# Turnstile_route1.net
KiCad netlist of a schematic drawn in EAGLE
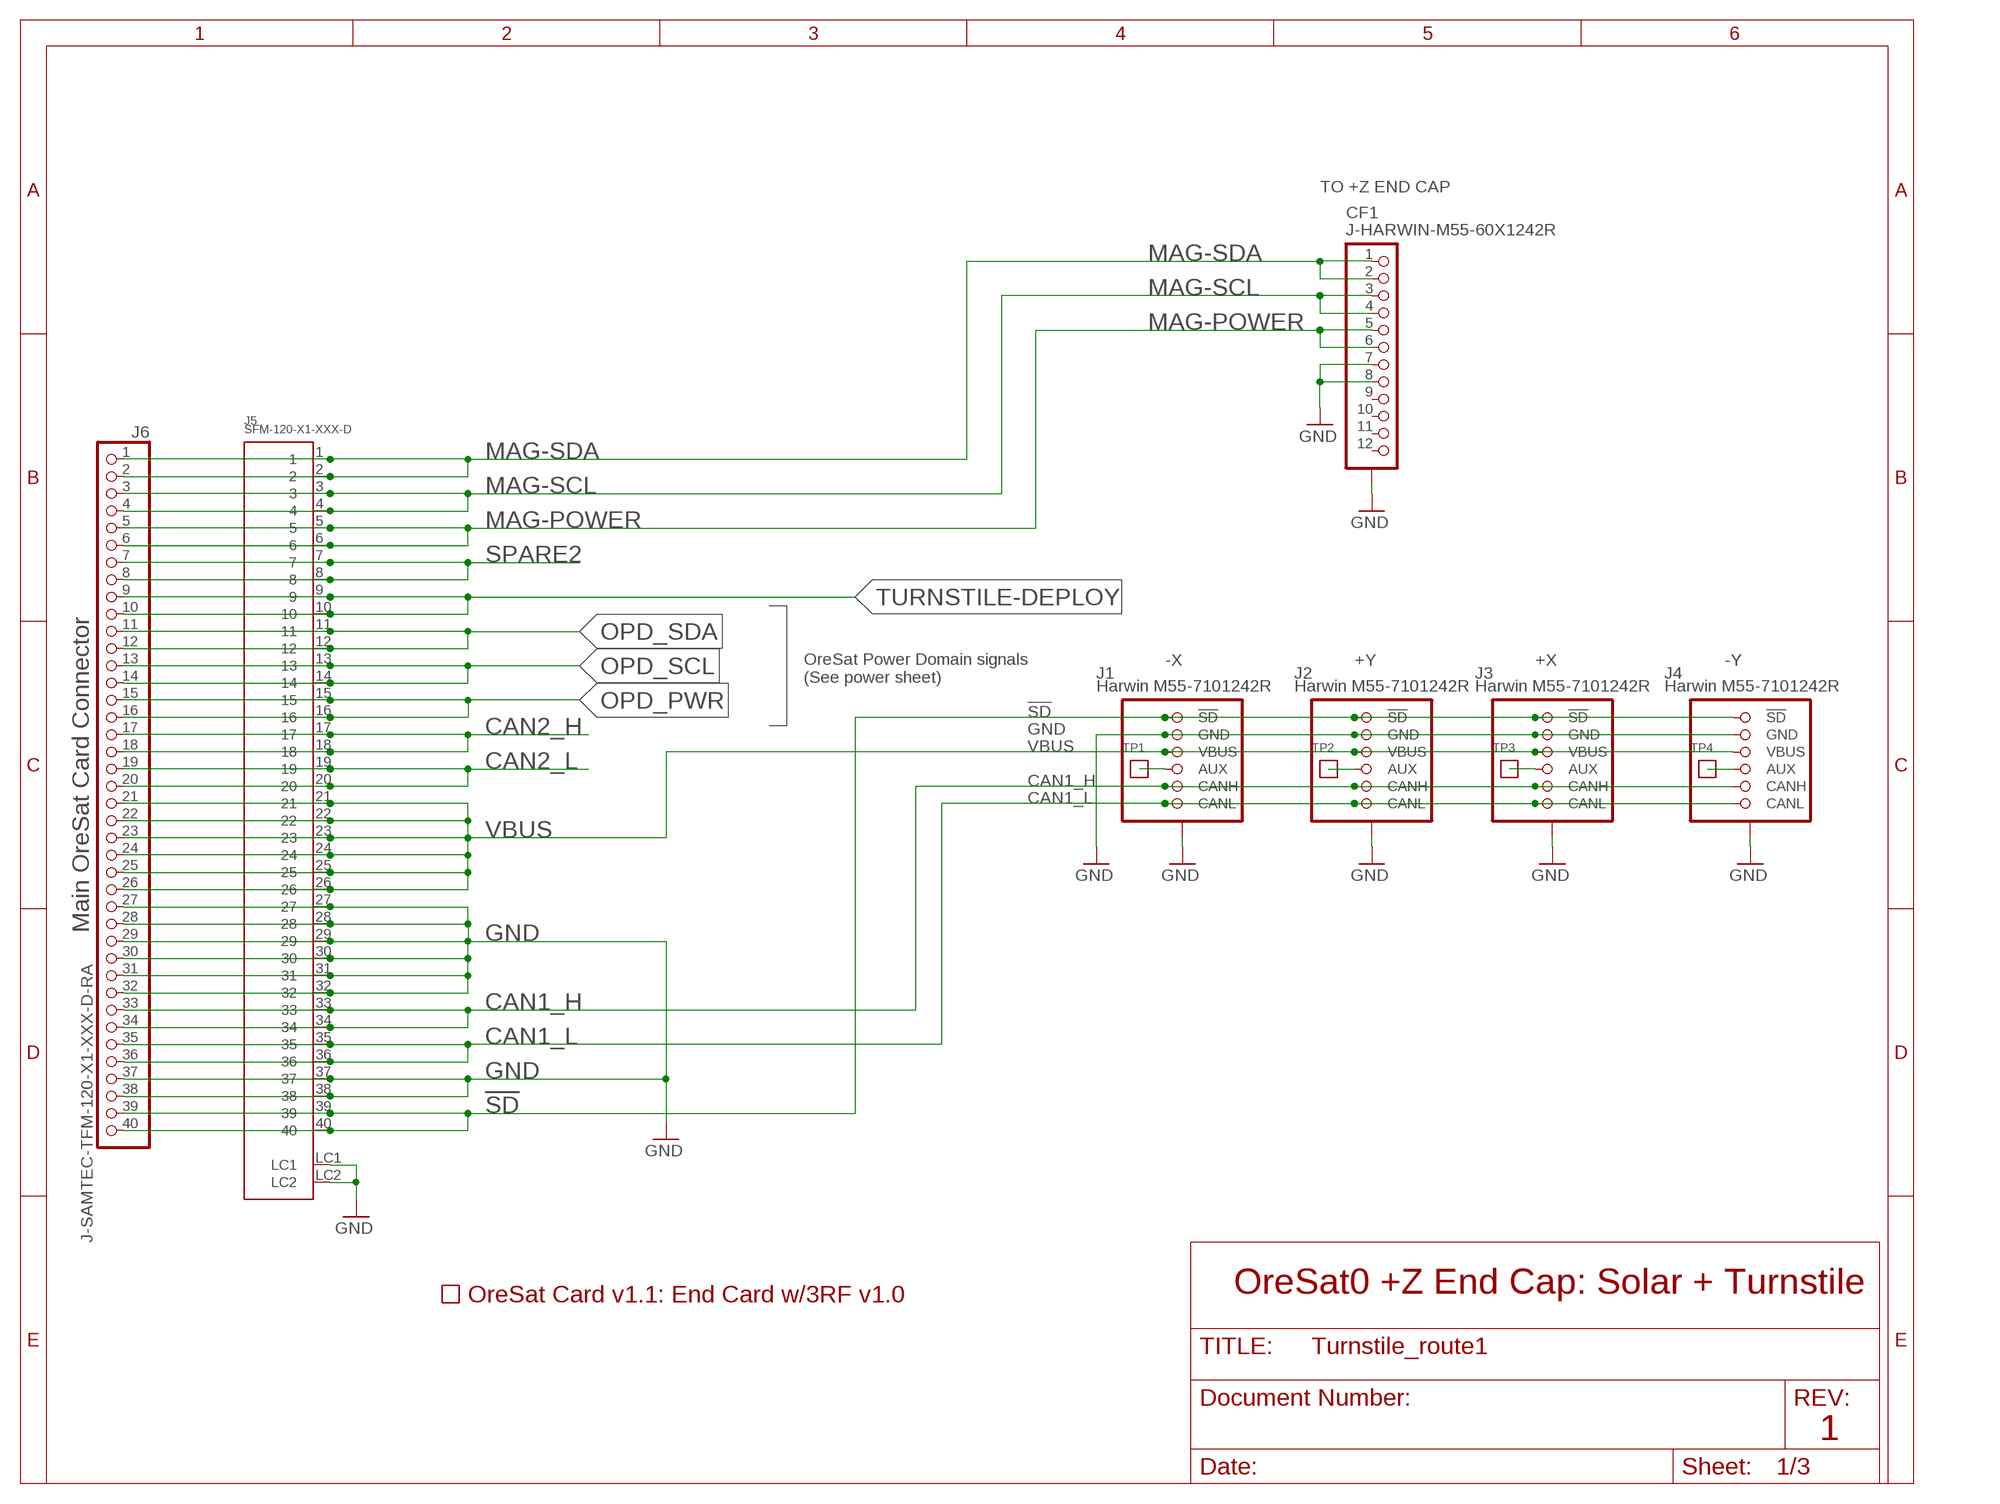
[diagram p0: schematic, sheet 1]
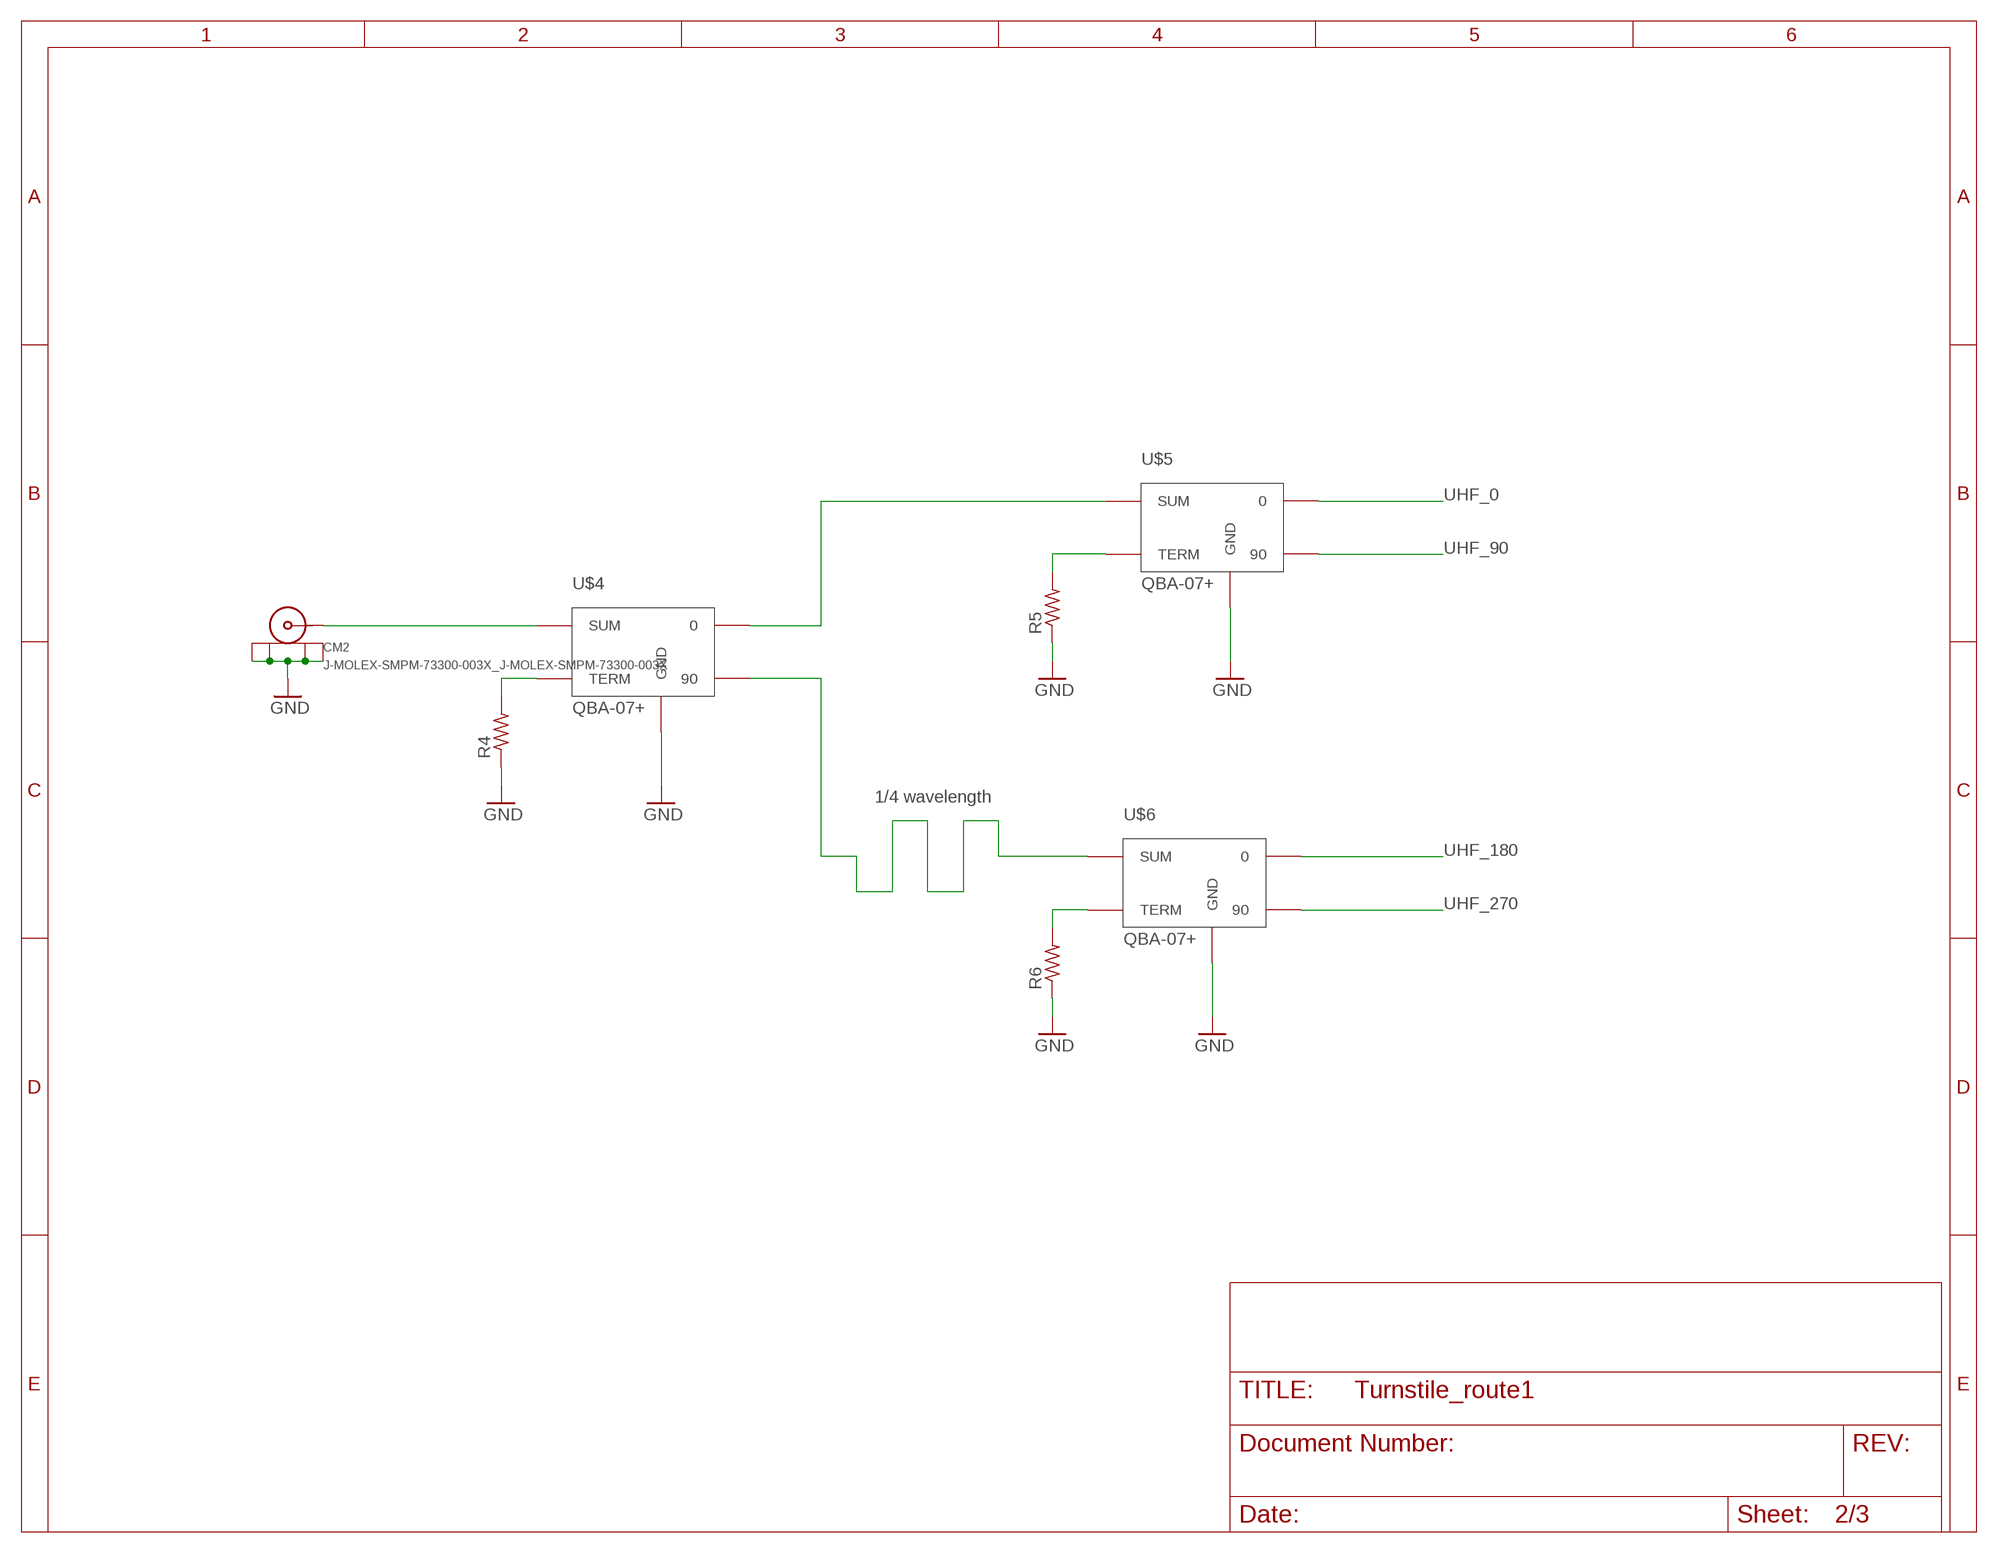
[diagram p1: schematic, sheet 2]
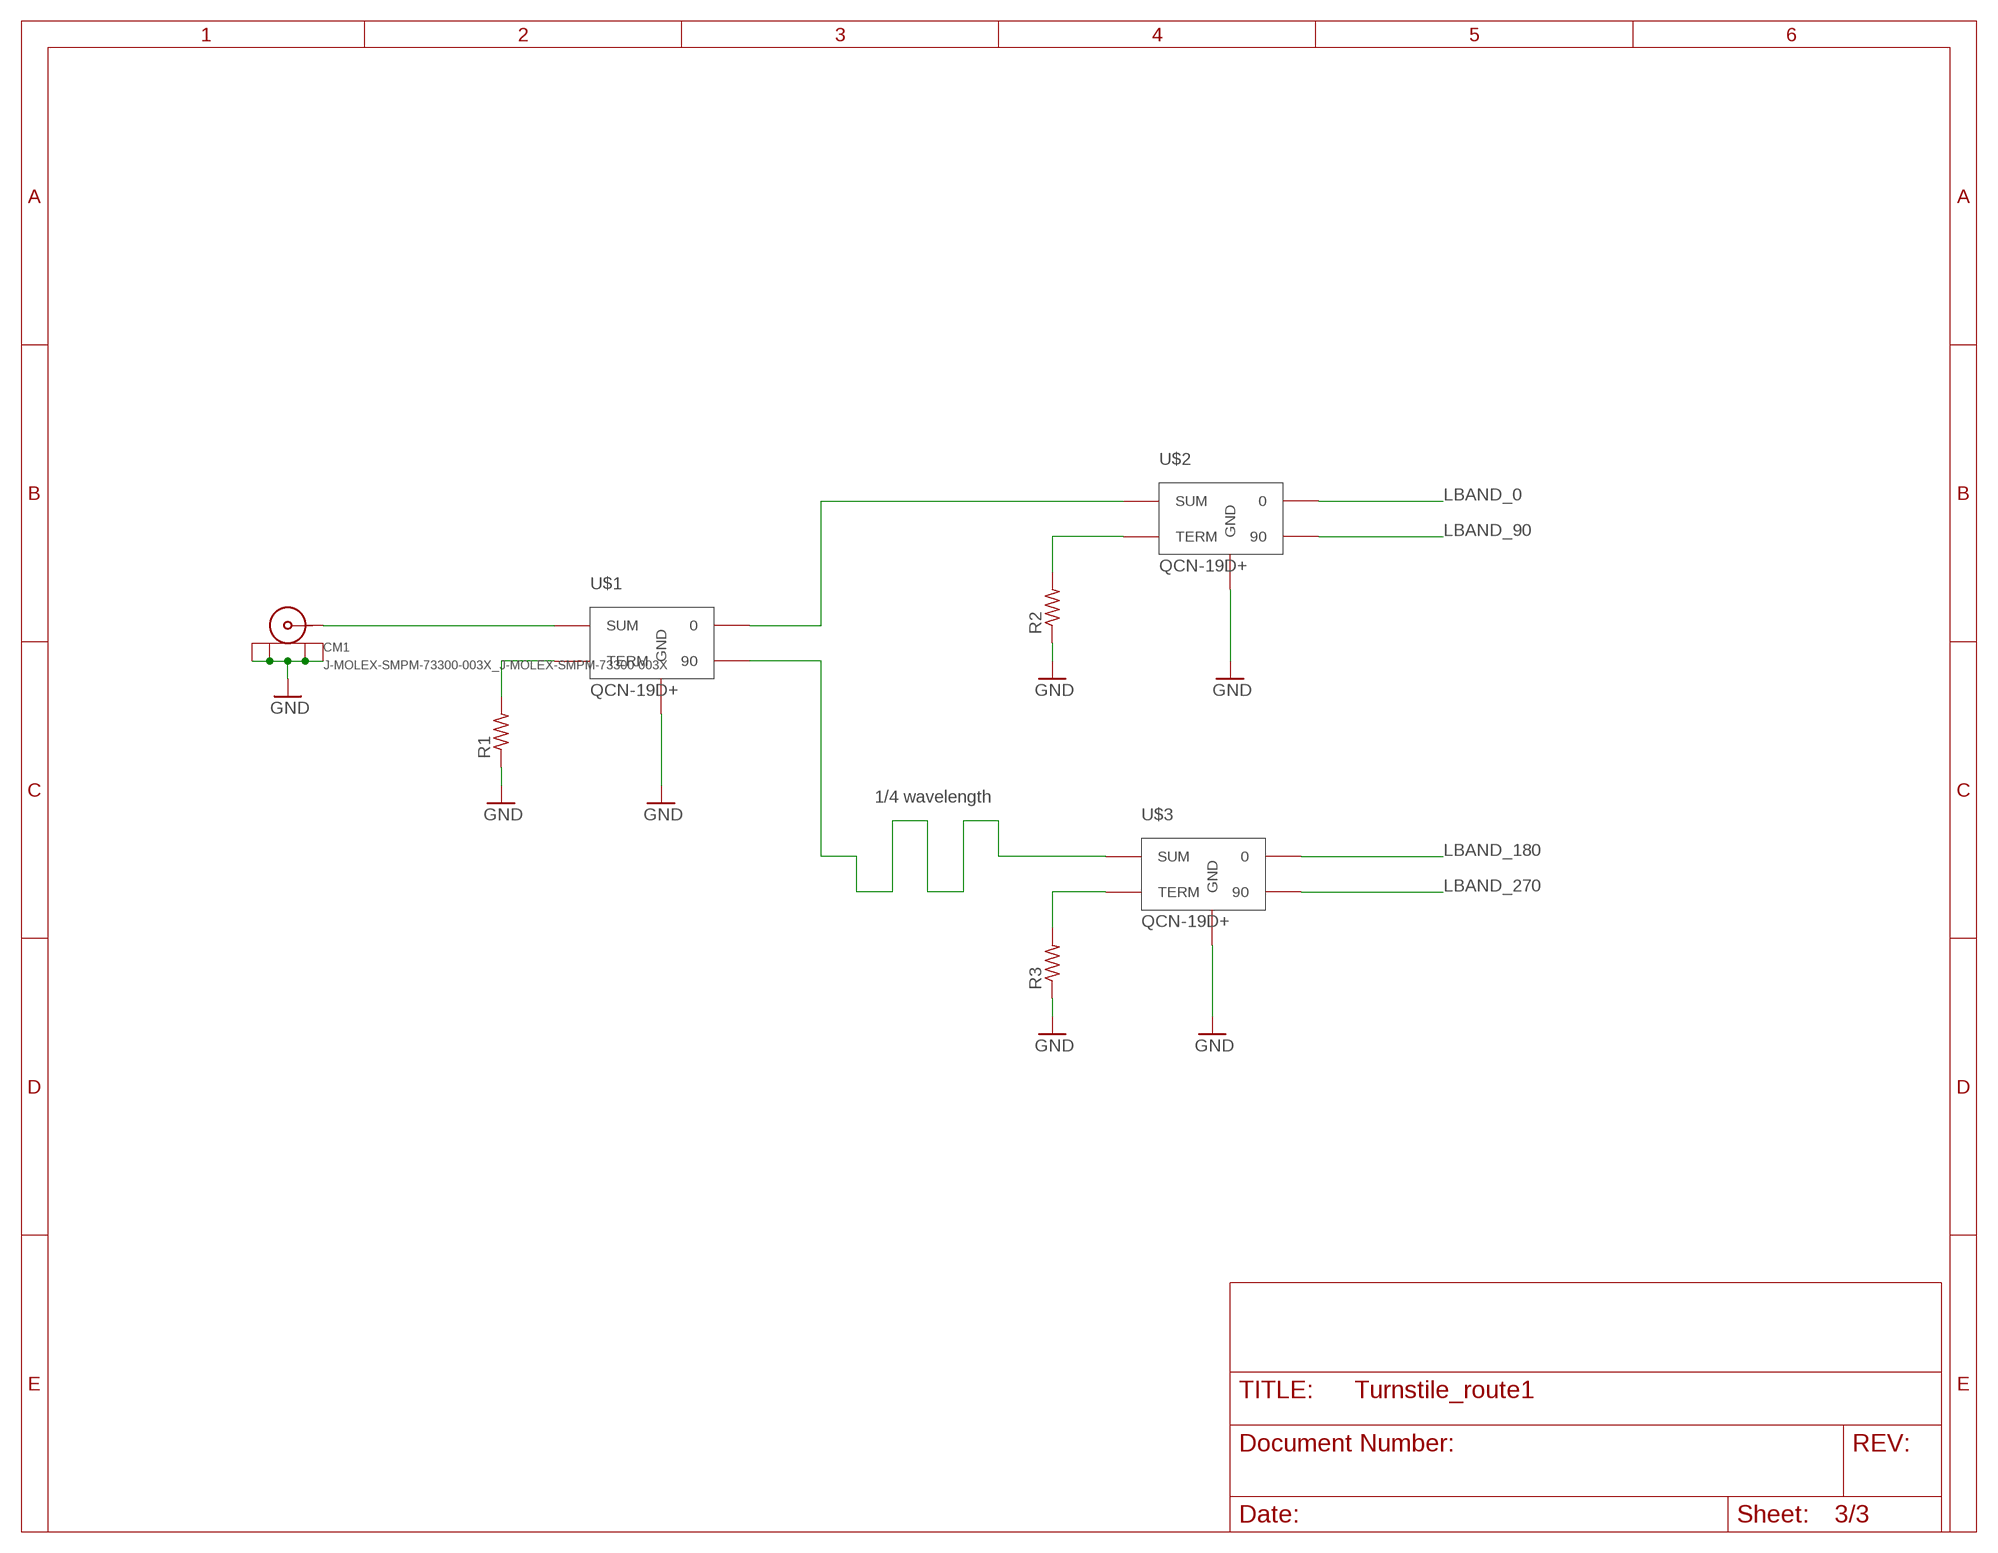
[diagram p2: schematic, sheet 3]

(export (version "E")
  (design (tool "Eeschema 10.0.6"))
  (components
    (comp (ref "CM1")
      (value "J-MOLEX-SMPM-73300-003X_J-MOLEX-SMPM-73300-003X")
      (footprint "eagle-import:J-MOLEX-SMPM-73300-003X_J-MOLEX-SMPM-073300-003X")
      (libsource (lib "eagle-import") (part "J-MOLEX-SMPM-73300-003X_J-MOLEX-SMPM-73300-003X"))
    )
    (comp (ref "R1")
      (value "R-US_0402-A-NOSILK")
      (footprint "eagle-import:.0402-A-NOSILK")
      (libsource (lib "eagle-import") (part "R-US_0402-A-NOSILK"))
    )
    (comp (ref "R2")
      (value "R-US_0402-A-NOSILK")
      (footprint "eagle-import:.0402-A-NOSILK")
      (libsource (lib "eagle-import") (part "R-US_0402-A-NOSILK"))
    )
    (comp (ref "R3")
      (value "R-US_0402-A-NOSILK")
      (footprint "eagle-import:.0402-A-NOSILK")
      (libsource (lib "eagle-import") (part "R-US_0402-A-NOSILK"))
    )
    (comp (ref "U$1")
      (value "QCN-19D+")
      (footprint "eagle-import:QVN-19D+")
      (libsource (lib "eagle-import") (part "QCN-19D+"))
    )
    (comp (ref "U$2")
      (value "QCN-19D+")
      (footprint "eagle-import:QVN-19D+")
      (libsource (lib "eagle-import") (part "QCN-19D+"))
    )
    (comp (ref "U$3")
      (value "QCN-19D+")
      (footprint "eagle-import:QVN-19D+")
      (libsource (lib "eagle-import") (part "QCN-19D+"))
    )
    (comp (ref "CF1")
      (value "J-HARWIN-M55-60X1242R")
      (footprint "eagle-import:HARWIN-M55-60X1242R")
      (libsource (lib "eagle-import") (part "J-HARWIN-M55-60X1242R"))
    )
    (comp (ref "J1")
      (value "Harwin M55-7101242R")
      (footprint "eagle-import:M55-7101242R")
      (libsource (lib "eagle-import") (part "SOLAR-CARD-CONNECTOR"))
    )
    (comp (ref "J2")
      (value "Harwin M55-7101242R")
      (footprint "eagle-import:M55-7101242R")
      (libsource (lib "eagle-import") (part "SOLAR-CARD-CONNECTOR"))
    )
    (comp (ref "J3")
      (value "Harwin M55-7101242R")
      (footprint "eagle-import:M55-7101242R")
      (libsource (lib "eagle-import") (part "SOLAR-CARD-CONNECTOR"))
    )
    (comp (ref "J4")
      (value "Harwin M55-7101242R")
      (footprint "eagle-import:M55-7101242R")
      (libsource (lib "eagle-import") (part "SOLAR-CARD-CONNECTOR"))
    )
    (comp (ref "J5")
      (value "SFM-120-X1-XXX-D")
      (footprint "eagle-import:SFM-120-X1-XXX-D")
      (libsource (lib "eagle-import") (part "SFM-120-X1-XXX-D"))
    )
    (comp (ref "J6")
      (value "J-SAMTEC-TFM-120-X1-XXX-D-RA")
      (footprint "eagle-import:J-SAMTEC-TFM-120-X1-XXX-D-RA")
      (fields (field (name "MFR") "Samtec") (field (name "MPN") "TFM-120-01-L-D-RA"))
      (libsource (lib "eagle-import") (part "J-SAMTEC-TFM-120-X1-XXX-D-RA"))
    )
    (comp (ref "PCB1")
      (value "ORESAT-CARD-V1.1-END-CARD-3RF-V1.0")
      (footprint "eagle-import:ORESAT-CARDV1.1-END-CARD-3RF-V1.0")
      (libsource (lib "eagle-import") (part "ORESAT-CARD-V1.1-END-CARD-3RF-V1.0"))
    )
    (comp (ref "TP1")
      (value "TEST-POINT-LARGE-SQUARE")
      (footprint "eagle-import:1X01")
      (libsource (lib "eagle-import") (part "TEST-POINT-LARGE-SQUARE"))
    )
    (comp (ref "TP2")
      (value "TEST-POINT-LARGE-SQUARE")
      (footprint "eagle-import:1X01")
      (libsource (lib "eagle-import") (part "TEST-POINT-LARGE-SQUARE"))
    )
    (comp (ref "TP3")
      (value "TEST-POINT-LARGE-SQUARE")
      (footprint "eagle-import:1X01")
      (libsource (lib "eagle-import") (part "TEST-POINT-LARGE-SQUARE"))
    )
    (comp (ref "TP4")
      (value "TEST-POINT-LARGE-SQUARE")
      (footprint "eagle-import:1X01")
      (libsource (lib "eagle-import") (part "TEST-POINT-LARGE-SQUARE"))
    )
    (comp (ref "CM2")
      (value "J-MOLEX-SMPM-73300-003X_J-MOLEX-SMPM-73300-003X")
      (footprint "eagle-import:J-MOLEX-SMPM-73300-003X_J-MOLEX-SMPM-073300-003X")
      (libsource (lib "eagle-import") (part "J-MOLEX-SMPM-73300-003X_J-MOLEX-SMPM-73300-003X"))
    )
    (comp (ref "R4")
      (value "R-US_0402-A-NOSILK")
      (footprint "eagle-import:.0402-A-NOSILK")
      (libsource (lib "eagle-import") (part "R-US_0402-A-NOSILK"))
    )
    (comp (ref "R5")
      (value "R-US_0402-A-NOSILK")
      (footprint "eagle-import:.0402-A-NOSILK")
      (libsource (lib "eagle-import") (part "R-US_0402-A-NOSILK"))
    )
    (comp (ref "R6")
      (value "R-US_0402-A-NOSILK")
      (footprint "eagle-import:.0402-A-NOSILK")
      (libsource (lib "eagle-import") (part "R-US_0402-A-NOSILK"))
    )
    (comp (ref "U$4")
      (value "QBA-07+")
      (footprint "eagle-import:QBA-07+")
      (libsource (lib "eagle-import") (part "QBA-07+"))
    )
    (comp (ref "U$5")
      (value "QBA-07+")
      (footprint "eagle-import:QBA-07+")
      (libsource (lib "eagle-import") (part "QBA-07+"))
    )
    (comp (ref "U$6")
      (value "QBA-07+")
      (footprint "eagle-import:QBA-07+")
      (libsource (lib "eagle-import") (part "QBA-07+"))
    )
  )
  (nets
    (net (code "1") (name "CAN1_H") (class "Default")
      (node (ref "J1") (pin "10") (pinfunction "CANH_10") (pintype "passive"))
      (node (ref "J1") (pin "9") (pinfunction "CANH_9") (pintype "passive"))
      (node (ref "J2") (pin "10") (pinfunction "CANH_10") (pintype "passive"))
      (node (ref "J2") (pin "9") (pinfunction "CANH_9") (pintype "passive"))
      (node (ref "J3") (pin "10") (pinfunction "CANH_10") (pintype "passive"))
      (node (ref "J3") (pin "9") (pinfunction "CANH_9") (pintype "passive"))
      (node (ref "J4") (pin "10") (pinfunction "CANH_10") (pintype "passive"))
      (node (ref "J4") (pin "9") (pinfunction "CANH_9") (pintype "passive"))
      (node (ref "J5") (pin "33") (pinfunction "33_33") (pintype "passive"))
      (node (ref "J5") (pin "34") (pinfunction "34_34") (pintype "passive"))
      (node (ref "J6") (pin "33") (pinfunction "33_33") (pintype "passive"))
      (node (ref "J6") (pin "34") (pinfunction "34_34") (pintype "passive"))
    )
    (net (code "2") (name "CAN1_L") (class "Default")
      (node (ref "J1") (pin "11") (pinfunction "CANL_11") (pintype "passive"))
      (node (ref "J1") (pin "12") (pinfunction "CANL_12") (pintype "passive"))
      (node (ref "J2") (pin "11") (pinfunction "CANL_11") (pintype "passive"))
      (node (ref "J2") (pin "12") (pinfunction "CANL_12") (pintype "passive"))
      (node (ref "J3") (pin "11") (pinfunction "CANL_11") (pintype "passive"))
      (node (ref "J3") (pin "12") (pinfunction "CANL_12") (pintype "passive"))
      (node (ref "J4") (pin "11") (pinfunction "CANL_11") (pintype "passive"))
      (node (ref "J4") (pin "12") (pinfunction "CANL_12") (pintype "passive"))
      (node (ref "J5") (pin "35") (pinfunction "35_35") (pintype "passive"))
      (node (ref "J5") (pin "36") (pinfunction "36_36") (pintype "passive"))
      (node (ref "J6") (pin "35") (pinfunction "35_35") (pintype "passive"))
      (node (ref "J6") (pin "36") (pinfunction "36_36") (pintype "passive"))
    )
    (net (code "3") (name "CAN2_H") (class "Default")
      (node (ref "J5") (pin "17") (pinfunction "17_17") (pintype "passive"))
      (node (ref "J5") (pin "18") (pinfunction "18_18") (pintype "passive"))
      (node (ref "J6") (pin "17") (pinfunction "17_17") (pintype "passive"))
      (node (ref "J6") (pin "18") (pinfunction "18_18") (pintype "passive"))
    )
    (net (code "4") (name "CAN2_L") (class "Default")
      (node (ref "J5") (pin "19") (pinfunction "19_19") (pintype "passive"))
      (node (ref "J5") (pin "20") (pinfunction "20_20") (pintype "passive"))
      (node (ref "J6") (pin "19") (pinfunction "19_19") (pintype "passive"))
      (node (ref "J6") (pin "20") (pinfunction "20_20") (pintype "passive"))
    )
    (net (code "5") (name "GND") (class "Default")
      (node (ref "CF1") (pin "7") (pinfunction "7_7") (pintype "passive"))
      (node (ref "CF1") (pin "8") (pinfunction "8_8") (pintype "passive"))
      (node (ref "CF1") (pin "P$1") (pinfunction "SHIELDS_P$1") (pintype "passive"))
      (node (ref "CF1") (pin "P$2") (pinfunction "SHIELDS_P$2") (pintype "passive"))
      (node (ref "CF1") (pin "P$3") (pinfunction "SHIELDS_P$3") (pintype "passive"))
      (node (ref "CF1") (pin "P$4") (pinfunction "SHIELDS_P$4") (pintype "passive"))
      (node (ref "CM1") (pin "P$1") (pinfunction "SHIELD3_P$1") (pintype "passive"))
      (node (ref "CM1") (pin "P$2") (pinfunction "SHIELD2_P$2") (pintype "passive"))
      (node (ref "CM1") (pin "P$3") (pinfunction "SHIELD1_P$3") (pintype "passive"))
      (node (ref "CM1") (pin "P$4") (pinfunction "SHIELD_P$4") (pintype "passive"))
      (node (ref "CM2") (pin "P$1") (pinfunction "SHIELD3_P$1") (pintype "passive"))
      (node (ref "CM2") (pin "P$2") (pinfunction "SHIELD2_P$2") (pintype "passive"))
      (node (ref "CM2") (pin "P$3") (pinfunction "SHIELD1_P$3") (pintype "passive"))
      (node (ref "CM2") (pin "P$4") (pinfunction "SHIELD_P$4") (pintype "passive"))
      (node (ref "J1") (pin "3") (pinfunction "GND_3") (pintype "passive"))
      (node (ref "J1") (pin "4") (pinfunction "GND_4") (pintype "passive"))
      (node (ref "J1") (pin "P$1") (pinfunction "SHIELD_P$1") (pintype "passive"))
      (node (ref "J1") (pin "P$2") (pinfunction "SHIELD_P$2") (pintype "passive"))
      (node (ref "J1") (pin "P$3") (pinfunction "SHIELD_P$3") (pintype "passive"))
      (node (ref "J1") (pin "P$4") (pinfunction "SHIELD_P$4") (pintype "passive"))
      (node (ref "J2") (pin "3") (pinfunction "GND_3") (pintype "passive"))
      (node (ref "J2") (pin "4") (pinfunction "GND_4") (pintype "passive"))
      (node (ref "J2") (pin "P$1") (pinfunction "SHIELD_P$1") (pintype "passive"))
      (node (ref "J2") (pin "P$2") (pinfunction "SHIELD_P$2") (pintype "passive"))
      (node (ref "J2") (pin "P$3") (pinfunction "SHIELD_P$3") (pintype "passive"))
      (node (ref "J2") (pin "P$4") (pinfunction "SHIELD_P$4") (pintype "passive"))
      (node (ref "J3") (pin "3") (pinfunction "GND_3") (pintype "passive"))
      (node (ref "J3") (pin "4") (pinfunction "GND_4") (pintype "passive"))
      (node (ref "J3") (pin "P$1") (pinfunction "SHIELD_P$1") (pintype "passive"))
      (node (ref "J3") (pin "P$2") (pinfunction "SHIELD_P$2") (pintype "passive"))
      (node (ref "J3") (pin "P$3") (pinfunction "SHIELD_P$3") (pintype "passive"))
      (node (ref "J3") (pin "P$4") (pinfunction "SHIELD_P$4") (pintype "passive"))
      (node (ref "J4") (pin "3") (pinfunction "GND_3") (pintype "passive"))
      (node (ref "J4") (pin "4") (pinfunction "GND_4") (pintype "passive"))
      (node (ref "J4") (pin "P$1") (pinfunction "SHIELD_P$1") (pintype "passive"))
      (node (ref "J4") (pin "P$2") (pinfunction "SHIELD_P$2") (pintype "passive"))
      (node (ref "J4") (pin "P$3") (pinfunction "SHIELD_P$3") (pintype "passive"))
      (node (ref "J4") (pin "P$4") (pinfunction "SHIELD_P$4") (pintype "passive"))
      (node (ref "J5") (pin "27") (pinfunction "27_27") (pintype "passive"))
      (node (ref "J5") (pin "28") (pinfunction "28_28") (pintype "passive"))
      (node (ref "J5") (pin "29") (pinfunction "29_29") (pintype "passive"))
      (node (ref "J5") (pin "30") (pinfunction "30_30") (pintype "passive"))
      (node (ref "J5") (pin "31") (pinfunction "31_31") (pintype "passive"))
      (node (ref "J5") (pin "32") (pinfunction "32_32") (pintype "passive"))
      (node (ref "J5") (pin "37") (pinfunction "37_37") (pintype "passive"))
      (node (ref "J5") (pin "38") (pinfunction "38_38") (pintype "passive"))
      (node (ref "J5") (pin "LC1") (pinfunction "LC1_LC1") (pintype "passive"))
      (node (ref "J5") (pin "LC2") (pinfunction "LC2_LC2") (pintype "passive"))
      (node (ref "J6") (pin "27") (pinfunction "27_27") (pintype "passive"))
      (node (ref "J6") (pin "28") (pinfunction "28_28") (pintype "passive"))
      (node (ref "J6") (pin "29") (pinfunction "29_29") (pintype "passive"))
      (node (ref "J6") (pin "30") (pinfunction "30_30") (pintype "passive"))
      (node (ref "J6") (pin "31") (pinfunction "31_31") (pintype "passive"))
      (node (ref "J6") (pin "32") (pinfunction "32_32") (pintype "passive"))
      (node (ref "J6") (pin "37") (pinfunction "37_37") (pintype "passive"))
      (node (ref "J6") (pin "38") (pinfunction "38_38") (pintype "passive"))
      (node (ref "R1") (pin "1") (pinfunction "1_1") (pintype "passive"))
      (node (ref "R2") (pin "1") (pinfunction "1_1") (pintype "passive"))
      (node (ref "R3") (pin "1") (pinfunction "1_1") (pintype "passive"))
      (node (ref "R4") (pin "1") (pinfunction "1_1") (pintype "passive"))
      (node (ref "R5") (pin "1") (pinfunction "1_1") (pintype "passive"))
      (node (ref "R6") (pin "1") (pinfunction "1_1") (pintype "passive"))
      (node (ref "U$1") (pin "P$2") (pinfunction "GND_P$2") (pintype "bidirectional"))
      (node (ref "U$1") (pin "P$5") (pinfunction "GND_P$5") (pintype "bidirectional"))
      (node (ref "U$2") (pin "P$2") (pinfunction "GND_P$2") (pintype "bidirectional"))
      (node (ref "U$2") (pin "P$5") (pinfunction "GND_P$5") (pintype "bidirectional"))
      (node (ref "U$3") (pin "P$2") (pinfunction "GND_P$2") (pintype "bidirectional"))
      (node (ref "U$3") (pin "P$5") (pinfunction "GND_P$5") (pintype "bidirectional"))
      (node (ref "U$4") (pin "P$11") (pinfunction "GND_P$11") (pintype "bidirectional"))
      (node (ref "U$4") (pin "P$2") (pinfunction "GND_P$2") (pintype "bidirectional"))
      (node (ref "U$4") (pin "P$3") (pinfunction "GND_P$3") (pintype "bidirectional"))
      (node (ref "U$4") (pin "P$4") (pinfunction "GND_P$4") (pintype "bidirectional"))
      (node (ref "U$4") (pin "P$7") (pinfunction "GND_P$7") (pintype "bidirectional"))
      (node (ref "U$4") (pin "P$8") (pinfunction "GND_P$8") (pintype "bidirectional"))
      (node (ref "U$4") (pin "P$9") (pinfunction "GND_P$9") (pintype "bidirectional"))
      (node (ref "U$5") (pin "P$11") (pinfunction "GND_P$11") (pintype "bidirectional"))
      (node (ref "U$5") (pin "P$2") (pinfunction "GND_P$2") (pintype "bidirectional"))
      (node (ref "U$5") (pin "P$3") (pinfunction "GND_P$3") (pintype "bidirectional"))
      (node (ref "U$5") (pin "P$4") (pinfunction "GND_P$4") (pintype "bidirectional"))
      (node (ref "U$5") (pin "P$7") (pinfunction "GND_P$7") (pintype "bidirectional"))
      (node (ref "U$5") (pin "P$8") (pinfunction "GND_P$8") (pintype "bidirectional"))
      (node (ref "U$5") (pin "P$9") (pinfunction "GND_P$9") (pintype "bidirectional"))
      (node (ref "U$6") (pin "P$11") (pinfunction "GND_P$11") (pintype "bidirectional"))
      (node (ref "U$6") (pin "P$2") (pinfunction "GND_P$2") (pintype "bidirectional"))
      (node (ref "U$6") (pin "P$3") (pinfunction "GND_P$3") (pintype "bidirectional"))
      (node (ref "U$6") (pin "P$4") (pinfunction "GND_P$4") (pintype "bidirectional"))
      (node (ref "U$6") (pin "P$7") (pinfunction "GND_P$7") (pintype "bidirectional"))
      (node (ref "U$6") (pin "P$8") (pinfunction "GND_P$8") (pintype "bidirectional"))
      (node (ref "U$6") (pin "P$9") (pinfunction "GND_P$9") (pintype "bidirectional"))
    )
    (net (code "6") (name "LBAND_0") (class "Default")
      (node (ref "U$2") (pin "P$4") (pinfunction "0_P$4") (pintype "bidirectional"))
    )
    (net (code "7") (name "LBAND_90") (class "Default")
      (node (ref "U$2") (pin "P$6") (pinfunction "90_P$6") (pintype "bidirectional"))
    )
    (net (code "8") (name "LBAND_180") (class "Default")
      (node (ref "U$3") (pin "P$4") (pinfunction "0_P$4") (pintype "bidirectional"))
    )
    (net (code "9") (name "LBAND_270") (class "Default")
      (node (ref "U$3") (pin "P$6") (pinfunction "90_P$6") (pintype "bidirectional"))
    )
    (net (code "10") (name "MAG-POWER") (class "Default")
      (node (ref "CF1") (pin "5") (pinfunction "5_5") (pintype "passive"))
      (node (ref "CF1") (pin "6") (pinfunction "6_6") (pintype "passive"))
      (node (ref "J5") (pin "5") (pinfunction "5_5") (pintype "passive"))
      (node (ref "J5") (pin "6") (pinfunction "6_6") (pintype "passive"))
      (node (ref "J6") (pin "5") (pinfunction "5_5") (pintype "passive"))
      (node (ref "J6") (pin "6") (pinfunction "6_6") (pintype "passive"))
    )
    (net (code "11") (name "MAG-SCL") (class "Default")
      (node (ref "CF1") (pin "3") (pinfunction "3_3") (pintype "passive"))
      (node (ref "CF1") (pin "4") (pinfunction "4_4") (pintype "passive"))
      (node (ref "J5") (pin "3") (pinfunction "3_3") (pintype "passive"))
      (node (ref "J5") (pin "4") (pinfunction "4_4") (pintype "passive"))
      (node (ref "J6") (pin "3") (pinfunction "3_3") (pintype "passive"))
      (node (ref "J6") (pin "4") (pinfunction "4_4") (pintype "passive"))
    )
    (net (code "12") (name "MAG-SDA") (class "Default")
      (node (ref "CF1") (pin "1") (pinfunction "1_1") (pintype "passive"))
      (node (ref "CF1") (pin "2") (pinfunction "2_2") (pintype "passive"))
      (node (ref "J5") (pin "1") (pinfunction "1_1") (pintype "passive"))
      (node (ref "J5") (pin "2") (pinfunction "2_2") (pintype "passive"))
      (node (ref "J6") (pin "1") (pinfunction "1_1") (pintype "passive"))
      (node (ref "J6") (pin "2") (pinfunction "2_2") (pintype "passive"))
    )
    (net (code "13") (name "Net-(CM1-CENTER)") (class "Default")
      (node (ref "CM1") (pin "RF") (pinfunction "CENTER_RF") (pintype "passive"))
      (node (ref "U$1") (pin "P$1") (pinfunction "SUM_P$1") (pintype "bidirectional"))
    )
    (net (code "14") (name "Net-(CM2-CENTER)") (class "Default")
      (node (ref "CM2") (pin "RF") (pinfunction "CENTER_RF") (pintype "passive"))
      (node (ref "U$4") (pin "P$1") (pinfunction "SUM_P$1") (pintype "bidirectional"))
    )
    (net (code "15") (name "Net-(J1-AUX-Pad7)") (class "Default")
      (node (ref "J1") (pin "7") (pinfunction "AUX_7") (pintype "passive"))
      (node (ref "J1") (pin "8") (pinfunction "AUX_8") (pintype "passive"))
      (node (ref "TP1") (pin "1") (pinfunction "1_1") (pintype "passive"))
    )
    (net (code "16") (name "Net-(J2-AUX-Pad7)") (class "Default")
      (node (ref "J2") (pin "7") (pinfunction "AUX_7") (pintype "passive"))
      (node (ref "J2") (pin "8") (pinfunction "AUX_8") (pintype "passive"))
      (node (ref "TP2") (pin "1") (pinfunction "1_1") (pintype "passive"))
    )
    (net (code "17") (name "Net-(J3-AUX-Pad7)") (class "Default")
      (node (ref "J3") (pin "7") (pinfunction "AUX_7") (pintype "passive"))
      (node (ref "J3") (pin "8") (pinfunction "AUX_8") (pintype "passive"))
      (node (ref "TP3") (pin "1") (pinfunction "1_1") (pintype "passive"))
    )
    (net (code "18") (name "Net-(J4-AUX-Pad7)") (class "Default")
      (node (ref "J4") (pin "7") (pinfunction "AUX_7") (pintype "passive"))
      (node (ref "J4") (pin "8") (pinfunction "AUX_8") (pintype "passive"))
      (node (ref "TP4") (pin "1") (pinfunction "1_1") (pintype "passive"))
    )
    (net (code "19") (name "Net-(U$1-0)") (class "Default")
      (node (ref "U$1") (pin "P$4") (pinfunction "0_P$4") (pintype "bidirectional"))
      (node (ref "U$2") (pin "P$1") (pinfunction "SUM_P$1") (pintype "bidirectional"))
    )
    (net (code "20") (name "Net-(U$1-90)") (class "Default")
      (node (ref "U$1") (pin "P$6") (pinfunction "90_P$6") (pintype "bidirectional"))
      (node (ref "U$3") (pin "P$1") (pinfunction "SUM_P$1") (pintype "bidirectional"))
    )
    (net (code "21") (name "Net-(U$1-TERM)") (class "Default")
      (node (ref "R1") (pin "2") (pinfunction "2_2") (pintype "passive"))
      (node (ref "U$1") (pin "P$3") (pinfunction "TERM_P$3") (pintype "bidirectional"))
    )
    (net (code "22") (name "Net-(U$2-TERM)") (class "Default")
      (node (ref "R2") (pin "2") (pinfunction "2_2") (pintype "passive"))
      (node (ref "U$2") (pin "P$3") (pinfunction "TERM_P$3") (pintype "bidirectional"))
    )
    (net (code "23") (name "Net-(U$3-TERM)") (class "Default")
      (node (ref "R3") (pin "2") (pinfunction "2_2") (pintype "passive"))
      (node (ref "U$3") (pin "P$3") (pinfunction "TERM_P$3") (pintype "bidirectional"))
    )
    (net (code "24") (name "Net-(U$4-0)") (class "Default")
      (node (ref "U$4") (pin "P$6") (pinfunction "0_P$6") (pintype "bidirectional"))
      (node (ref "U$5") (pin "P$1") (pinfunction "SUM_P$1") (pintype "bidirectional"))
    )
    (net (code "25") (name "Net-(U$4-90)") (class "Default")
      (node (ref "U$4") (pin "P$10") (pinfunction "90_P$10") (pintype "bidirectional"))
      (node (ref "U$6") (pin "P$1") (pinfunction "SUM_P$1") (pintype "bidirectional"))
    )
    (net (code "26") (name "Net-(U$4-TERM)") (class "Default")
      (node (ref "R4") (pin "2") (pinfunction "2_2") (pintype "passive"))
      (node (ref "U$4") (pin "P$5") (pinfunction "TERM_P$5") (pintype "bidirectional"))
    )
    (net (code "27") (name "Net-(U$5-TERM)") (class "Default")
      (node (ref "R5") (pin "2") (pinfunction "2_2") (pintype "passive"))
      (node (ref "U$5") (pin "P$5") (pinfunction "TERM_P$5") (pintype "bidirectional"))
    )
    (net (code "28") (name "Net-(U$6-TERM)") (class "Default")
      (node (ref "R6") (pin "2") (pinfunction "2_2") (pintype "passive"))
      (node (ref "U$6") (pin "P$5") (pinfunction "TERM_P$5") (pintype "bidirectional"))
    )
    (net (code "29") (name "OPD_PWR") (class "Default")
      (node (ref "J5") (pin "15") (pinfunction "15_15") (pintype "passive"))
      (node (ref "J5") (pin "16") (pinfunction "16_16") (pintype "passive"))
      (node (ref "J6") (pin "15") (pinfunction "15_15") (pintype "passive"))
      (node (ref "J6") (pin "16") (pinfunction "16_16") (pintype "passive"))
    )
    (net (code "30") (name "OPD_SCL") (class "Default")
      (node (ref "J5") (pin "13") (pinfunction "13_13") (pintype "passive"))
      (node (ref "J5") (pin "14") (pinfunction "14_14") (pintype "passive"))
      (node (ref "J6") (pin "13") (pinfunction "13_13") (pintype "passive"))
      (node (ref "J6") (pin "14") (pinfunction "14_14") (pintype "passive"))
    )
    (net (code "31") (name "OPD_SDA") (class "Default")
      (node (ref "J5") (pin "11") (pinfunction "11_11") (pintype "passive"))
      (node (ref "J5") (pin "12") (pinfunction "12_12") (pintype "passive"))
      (node (ref "J6") (pin "11") (pinfunction "11_11") (pintype "passive"))
      (node (ref "J6") (pin "12") (pinfunction "12_12") (pintype "passive"))
    )
    (net (code "32") (name "SPARE2") (class "Default")
      (node (ref "J5") (pin "7") (pinfunction "7_7") (pintype "passive"))
      (node (ref "J5") (pin "8") (pinfunction "8_8") (pintype "passive"))
      (node (ref "J6") (pin "7") (pinfunction "7_7") (pintype "passive"))
      (node (ref "J6") (pin "8") (pinfunction "8_8") (pintype "passive"))
    )
    (net (code "33") (name "TURNSTILE-DEPLOY") (class "Default")
      (node (ref "J5") (pin "10") (pinfunction "10_10") (pintype "passive"))
      (node (ref "J5") (pin "9") (pinfunction "9_9") (pintype "passive"))
      (node (ref "J6") (pin "10") (pinfunction "10_10") (pintype "passive"))
      (node (ref "J6") (pin "9") (pinfunction "9_9") (pintype "passive"))
    )
    (net (code "34") (name "UHF_0") (class "Default")
      (node (ref "U$5") (pin "P$6") (pinfunction "0_P$6") (pintype "bidirectional"))
    )
    (net (code "35") (name "UHF_90") (class "Default")
      (node (ref "U$5") (pin "P$10") (pinfunction "90_P$10") (pintype "bidirectional"))
    )
    (net (code "36") (name "UHF_180") (class "Default")
      (node (ref "U$6") (pin "P$6") (pinfunction "0_P$6") (pintype "bidirectional"))
    )
    (net (code "37") (name "UHF_270") (class "Default")
      (node (ref "U$6") (pin "P$10") (pinfunction "90_P$10") (pintype "bidirectional"))
    )
    (net (code "38") (name "VBUS") (class "Default")
      (node (ref "J1") (pin "5") (pinfunction "VBUS_5") (pintype "passive"))
      (node (ref "J1") (pin "6") (pinfunction "VBUS_6") (pintype "passive"))
      (node (ref "J2") (pin "5") (pinfunction "VBUS_5") (pintype "passive"))
      (node (ref "J2") (pin "6") (pinfunction "VBUS_6") (pintype "passive"))
      (node (ref "J3") (pin "5") (pinfunction "VBUS_5") (pintype "passive"))
      (node (ref "J3") (pin "6") (pinfunction "VBUS_6") (pintype "passive"))
      (node (ref "J4") (pin "5") (pinfunction "VBUS_5") (pintype "passive"))
      (node (ref "J4") (pin "6") (pinfunction "VBUS_6") (pintype "passive"))
      (node (ref "J5") (pin "21") (pinfunction "21_21") (pintype "passive"))
      (node (ref "J5") (pin "22") (pinfunction "22_22") (pintype "passive"))
      (node (ref "J5") (pin "23") (pinfunction "23_23") (pintype "passive"))
      (node (ref "J5") (pin "24") (pinfunction "24_24") (pintype "passive"))
      (node (ref "J5") (pin "25") (pinfunction "25_25") (pintype "passive"))
      (node (ref "J5") (pin "26") (pinfunction "26_26") (pintype "passive"))
      (node (ref "J6") (pin "21") (pinfunction "21_21") (pintype "passive"))
      (node (ref "J6") (pin "22") (pinfunction "22_22") (pintype "passive"))
      (node (ref "J6") (pin "23") (pinfunction "23_23") (pintype "passive"))
      (node (ref "J6") (pin "24") (pinfunction "24_24") (pintype "passive"))
      (node (ref "J6") (pin "25") (pinfunction "25_25") (pintype "passive"))
      (node (ref "J6") (pin "26") (pinfunction "26_26") (pintype "passive"))
    )
    (net (code "39") (name "unconnected-(CF1-Pad9)") (class "Default")
      (node (ref "CF1") (pin "9") (pinfunction "9_9") (pintype "passive"))
    )
    (net (code "40") (name "unconnected-(CF1-Pad10)") (class "Default")
      (node (ref "CF1") (pin "10") (pinfunction "10_10") (pintype "passive"))
    )
    (net (code "41") (name "unconnected-(CF1-Pad11)") (class "Default")
      (node (ref "CF1") (pin "11") (pinfunction "11_11") (pintype "passive"))
    )
    (net (code "42") (name "unconnected-(CF1-Pad12)") (class "Default")
      (node (ref "CF1") (pin "12") (pinfunction "12_12") (pintype "passive"))
    )
    (net (code "43") (name "~{SD}") (class "Default")
      (node (ref "J1") (pin "1") (pinfunction "~{SD}_1") (pintype "passive"))
      (node (ref "J1") (pin "2") (pinfunction "~{SD}_2") (pintype "passive"))
      (node (ref "J2") (pin "1") (pinfunction "~{SD}_1") (pintype "passive"))
      (node (ref "J2") (pin "2") (pinfunction "~{SD}_2") (pintype "passive"))
      (node (ref "J3") (pin "1") (pinfunction "~{SD}_1") (pintype "passive"))
      (node (ref "J3") (pin "2") (pinfunction "~{SD}_2") (pintype "passive"))
      (node (ref "J4") (pin "1") (pinfunction "~{SD}_1") (pintype "passive"))
      (node (ref "J4") (pin "2") (pinfunction "~{SD}_2") (pintype "passive"))
      (node (ref "J5") (pin "39") (pinfunction "39_39") (pintype "passive"))
      (node (ref "J5") (pin "40") (pinfunction "40_40") (pintype "passive"))
      (node (ref "J6") (pin "39") (pinfunction "39_39") (pintype "passive"))
      (node (ref "J6") (pin "40") (pinfunction "40_40") (pintype "passive"))
    )
  )
)
